# BeagleV_Chew_Toy.net
KiCad netlist of a schematic drawn in EAGLE
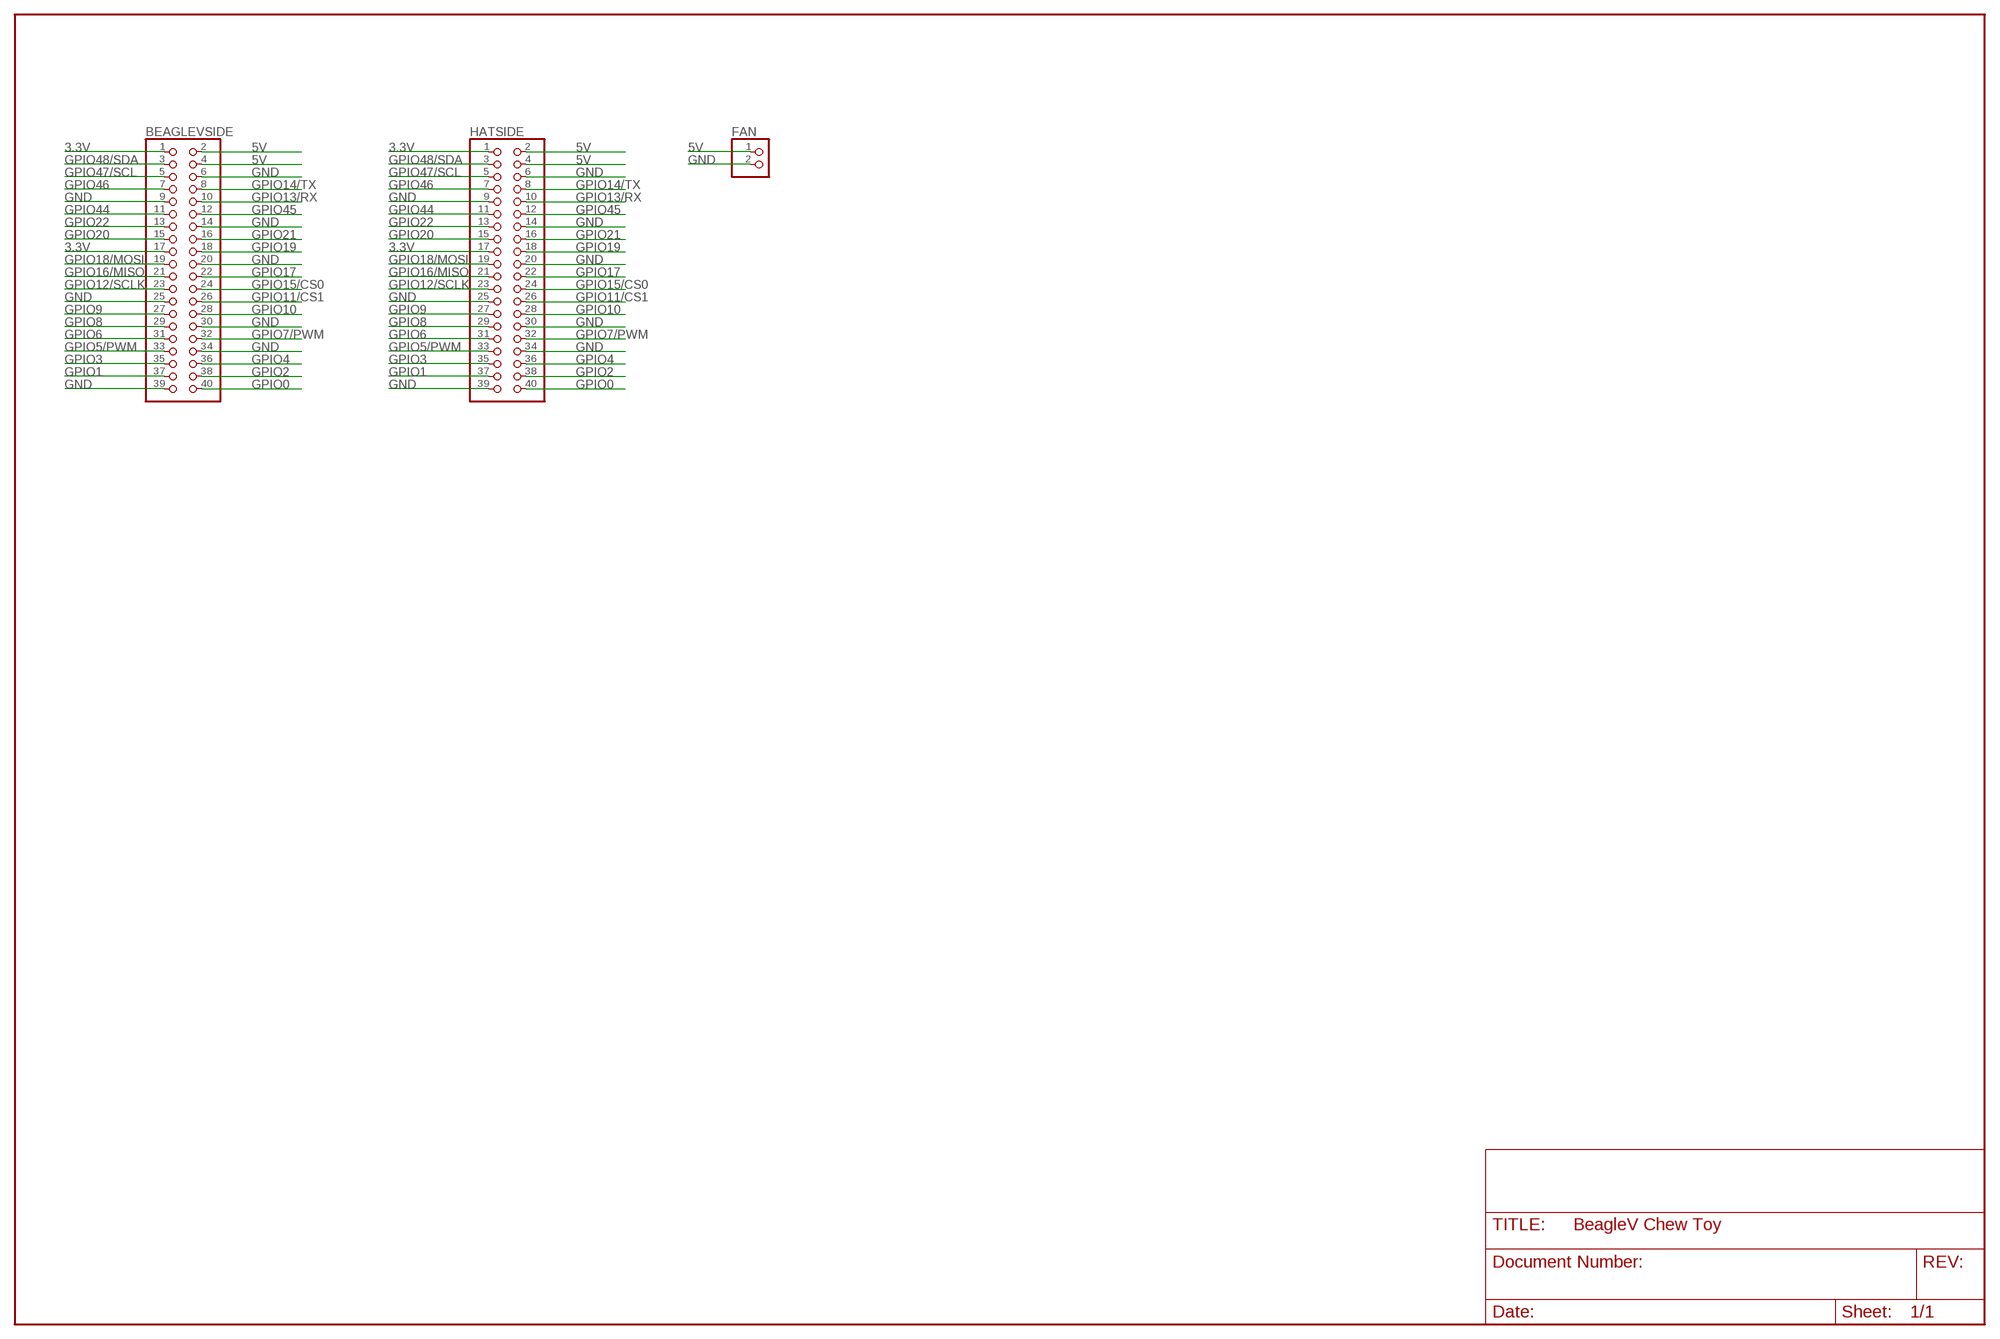
[diagram p0: schematic, sheet 1]

(export (version "E")
  (design (tool "Eeschema 10.0.6"))
  (components
    (comp (ref "BEAGLEVSIDE")
      (value "PINHD-2X20")
      (footprint "eagle-import:2X20")
      (libsource (lib "eagle-import") (part "PINHD-2X20"))
    )
    (comp (ref "FAN")
      (value "PINHD-1X2")
      (footprint "eagle-import:1X02")
      (libsource (lib "eagle-import") (part "PINHD-1X2"))
    )
    (comp (ref "HATSIDE")
      (value "PINHD-2X20-BIG")
      (footprint "eagle-import:2X20-BIG")
      (libsource (lib "eagle-import") (part "adafruit_PINHD-2X20-BIG"))
    )
  )
  (nets
    (net (code "1") (name "/3.3V") (class "Default")
      (node (ref "BEAGLEVSIDE") (pin "1") (pinfunction "1_1") (pintype "passive"))
      (node (ref "BEAGLEVSIDE") (pin "17") (pinfunction "17_17") (pintype "passive"))
      (node (ref "HATSIDE") (pin "1") (pinfunction "1_1") (pintype "passive"))
      (node (ref "HATSIDE") (pin "17") (pinfunction "17_17") (pintype "passive"))
    )
    (net (code "2") (name "/5V") (class "Default")
      (node (ref "BEAGLEVSIDE") (pin "2") (pinfunction "2_2") (pintype "passive"))
      (node (ref "BEAGLEVSIDE") (pin "4") (pinfunction "4_4") (pintype "passive"))
      (node (ref "FAN") (pin "1") (pinfunction "1_1") (pintype "passive"))
      (node (ref "HATSIDE") (pin "2") (pinfunction "2_2") (pintype "passive"))
      (node (ref "HATSIDE") (pin "4") (pinfunction "4_4") (pintype "passive"))
    )
    (net (code "3") (name "/GND") (class "Default")
      (node (ref "BEAGLEVSIDE") (pin "14") (pinfunction "14_14") (pintype "passive"))
      (node (ref "BEAGLEVSIDE") (pin "20") (pinfunction "20_20") (pintype "passive"))
      (node (ref "BEAGLEVSIDE") (pin "25") (pinfunction "25_25") (pintype "passive"))
      (node (ref "BEAGLEVSIDE") (pin "30") (pinfunction "30_30") (pintype "passive"))
      (node (ref "BEAGLEVSIDE") (pin "34") (pinfunction "34_34") (pintype "passive"))
      (node (ref "BEAGLEVSIDE") (pin "39") (pinfunction "39_39") (pintype "passive"))
      (node (ref "BEAGLEVSIDE") (pin "6") (pinfunction "6_6") (pintype "passive"))
      (node (ref "BEAGLEVSIDE") (pin "9") (pinfunction "9_9") (pintype "passive"))
      (node (ref "FAN") (pin "2") (pinfunction "2_2") (pintype "passive"))
      (node (ref "HATSIDE") (pin "14") (pinfunction "14_14") (pintype "passive"))
      (node (ref "HATSIDE") (pin "20") (pinfunction "20_20") (pintype "passive"))
      (node (ref "HATSIDE") (pin "25") (pinfunction "25_25") (pintype "passive"))
      (node (ref "HATSIDE") (pin "30") (pinfunction "30_30") (pintype "passive"))
      (node (ref "HATSIDE") (pin "34") (pinfunction "34_34") (pintype "passive"))
      (node (ref "HATSIDE") (pin "39") (pinfunction "39_39") (pintype "passive"))
      (node (ref "HATSIDE") (pin "6") (pinfunction "6_6") (pintype "passive"))
      (node (ref "HATSIDE") (pin "9") (pinfunction "9_9") (pintype "passive"))
    )
    (net (code "4") (name "/GPIO0") (class "Default")
      (node (ref "BEAGLEVSIDE") (pin "40") (pinfunction "40_40") (pintype "passive"))
      (node (ref "HATSIDE") (pin "40") (pinfunction "40_40") (pintype "passive"))
    )
    (net (code "5") (name "/GPIO1") (class "Default")
      (node (ref "BEAGLEVSIDE") (pin "37") (pinfunction "37_37") (pintype "passive"))
      (node (ref "HATSIDE") (pin "37") (pinfunction "37_37") (pintype "passive"))
    )
    (net (code "6") (name "/GPIO2") (class "Default")
      (node (ref "BEAGLEVSIDE") (pin "38") (pinfunction "38_38") (pintype "passive"))
      (node (ref "HATSIDE") (pin "38") (pinfunction "38_38") (pintype "passive"))
    )
    (net (code "7") (name "/GPIO3") (class "Default")
      (node (ref "BEAGLEVSIDE") (pin "35") (pinfunction "35_35") (pintype "passive"))
      (node (ref "HATSIDE") (pin "35") (pinfunction "35_35") (pintype "passive"))
    )
    (net (code "8") (name "/GPIO4") (class "Default")
      (node (ref "BEAGLEVSIDE") (pin "36") (pinfunction "36_36") (pintype "passive"))
      (node (ref "HATSIDE") (pin "36") (pinfunction "36_36") (pintype "passive"))
    )
    (net (code "9") (name "/GPIO5{slash}PWM") (class "Default")
      (node (ref "BEAGLEVSIDE") (pin "33") (pinfunction "33_33") (pintype "passive"))
      (node (ref "HATSIDE") (pin "33") (pinfunction "33_33") (pintype "passive"))
    )
    (net (code "10") (name "/GPIO6") (class "Default")
      (node (ref "BEAGLEVSIDE") (pin "31") (pinfunction "31_31") (pintype "passive"))
      (node (ref "HATSIDE") (pin "31") (pinfunction "31_31") (pintype "passive"))
    )
    (net (code "11") (name "/GPIO7{slash}PWM") (class "Default")
      (node (ref "BEAGLEVSIDE") (pin "32") (pinfunction "32_32") (pintype "passive"))
      (node (ref "HATSIDE") (pin "32") (pinfunction "32_32") (pintype "passive"))
    )
    (net (code "12") (name "/GPIO8") (class "Default")
      (node (ref "BEAGLEVSIDE") (pin "29") (pinfunction "29_29") (pintype "passive"))
      (node (ref "HATSIDE") (pin "29") (pinfunction "29_29") (pintype "passive"))
    )
    (net (code "13") (name "/GPIO9") (class "Default")
      (node (ref "BEAGLEVSIDE") (pin "27") (pinfunction "27_27") (pintype "passive"))
      (node (ref "HATSIDE") (pin "27") (pinfunction "27_27") (pintype "passive"))
    )
    (net (code "14") (name "/GPIO10") (class "Default")
      (node (ref "BEAGLEVSIDE") (pin "28") (pinfunction "28_28") (pintype "passive"))
      (node (ref "HATSIDE") (pin "28") (pinfunction "28_28") (pintype "passive"))
    )
    (net (code "15") (name "/GPIO11{slash}CS1") (class "Default")
      (node (ref "BEAGLEVSIDE") (pin "26") (pinfunction "26_26") (pintype "passive"))
      (node (ref "HATSIDE") (pin "26") (pinfunction "26_26") (pintype "passive"))
    )
    (net (code "16") (name "/GPIO12{slash}SCLK") (class "Default")
      (node (ref "BEAGLEVSIDE") (pin "23") (pinfunction "23_23") (pintype "passive"))
      (node (ref "HATSIDE") (pin "23") (pinfunction "23_23") (pintype "passive"))
    )
    (net (code "17") (name "/GPIO13{slash}RX") (class "Default")
      (node (ref "BEAGLEVSIDE") (pin "10") (pinfunction "10_10") (pintype "passive"))
      (node (ref "HATSIDE") (pin "10") (pinfunction "10_10") (pintype "passive"))
    )
    (net (code "18") (name "/GPIO14{slash}TX") (class "Default")
      (node (ref "BEAGLEVSIDE") (pin "8") (pinfunction "8_8") (pintype "passive"))
      (node (ref "HATSIDE") (pin "8") (pinfunction "8_8") (pintype "passive"))
    )
    (net (code "19") (name "/GPIO15{slash}CS0") (class "Default")
      (node (ref "BEAGLEVSIDE") (pin "24") (pinfunction "24_24") (pintype "passive"))
      (node (ref "HATSIDE") (pin "24") (pinfunction "24_24") (pintype "passive"))
    )
    (net (code "20") (name "/GPIO16{slash}MISO") (class "Default")
      (node (ref "BEAGLEVSIDE") (pin "21") (pinfunction "21_21") (pintype "passive"))
      (node (ref "HATSIDE") (pin "21") (pinfunction "21_21") (pintype "passive"))
    )
    (net (code "21") (name "/GPIO17") (class "Default")
      (node (ref "BEAGLEVSIDE") (pin "22") (pinfunction "22_22") (pintype "passive"))
      (node (ref "HATSIDE") (pin "22") (pinfunction "22_22") (pintype "passive"))
    )
    (net (code "22") (name "/GPIO18{slash}MOSI") (class "Default")
      (node (ref "BEAGLEVSIDE") (pin "19") (pinfunction "19_19") (pintype "passive"))
      (node (ref "HATSIDE") (pin "19") (pinfunction "19_19") (pintype "passive"))
    )
    (net (code "23") (name "/GPIO19") (class "Default")
      (node (ref "BEAGLEVSIDE") (pin "18") (pinfunction "18_18") (pintype "passive"))
      (node (ref "HATSIDE") (pin "18") (pinfunction "18_18") (pintype "passive"))
    )
    (net (code "24") (name "/GPIO20") (class "Default")
      (node (ref "BEAGLEVSIDE") (pin "15") (pinfunction "15_15") (pintype "passive"))
      (node (ref "HATSIDE") (pin "15") (pinfunction "15_15") (pintype "passive"))
    )
    (net (code "25") (name "/GPIO21") (class "Default")
      (node (ref "BEAGLEVSIDE") (pin "16") (pinfunction "16_16") (pintype "passive"))
      (node (ref "HATSIDE") (pin "16") (pinfunction "16_16") (pintype "passive"))
    )
    (net (code "26") (name "/GPIO22") (class "Default")
      (node (ref "BEAGLEVSIDE") (pin "13") (pinfunction "13_13") (pintype "passive"))
      (node (ref "HATSIDE") (pin "13") (pinfunction "13_13") (pintype "passive"))
    )
    (net (code "27") (name "/GPIO44") (class "Default")
      (node (ref "BEAGLEVSIDE") (pin "11") (pinfunction "11_11") (pintype "passive"))
      (node (ref "HATSIDE") (pin "11") (pinfunction "11_11") (pintype "passive"))
    )
    (net (code "28") (name "/GPIO45") (class "Default")
      (node (ref "BEAGLEVSIDE") (pin "12") (pinfunction "12_12") (pintype "passive"))
      (node (ref "HATSIDE") (pin "12") (pinfunction "12_12") (pintype "passive"))
    )
    (net (code "29") (name "/GPIO46") (class "Default")
      (node (ref "BEAGLEVSIDE") (pin "7") (pinfunction "7_7") (pintype "passive"))
      (node (ref "HATSIDE") (pin "7") (pinfunction "7_7") (pintype "passive"))
    )
    (net (code "30") (name "/GPIO47{slash}SCL") (class "Default")
      (node (ref "BEAGLEVSIDE") (pin "5") (pinfunction "5_5") (pintype "passive"))
      (node (ref "HATSIDE") (pin "5") (pinfunction "5_5") (pintype "passive"))
    )
    (net (code "31") (name "/GPIO48{slash}SDA") (class "Default")
      (node (ref "BEAGLEVSIDE") (pin "3") (pinfunction "3_3") (pintype "passive"))
      (node (ref "HATSIDE") (pin "3") (pinfunction "3_3") (pintype "passive"))
    )
  )
)
